# power_board.net
KiCad netlist of a schematic drawn in Altium Designer
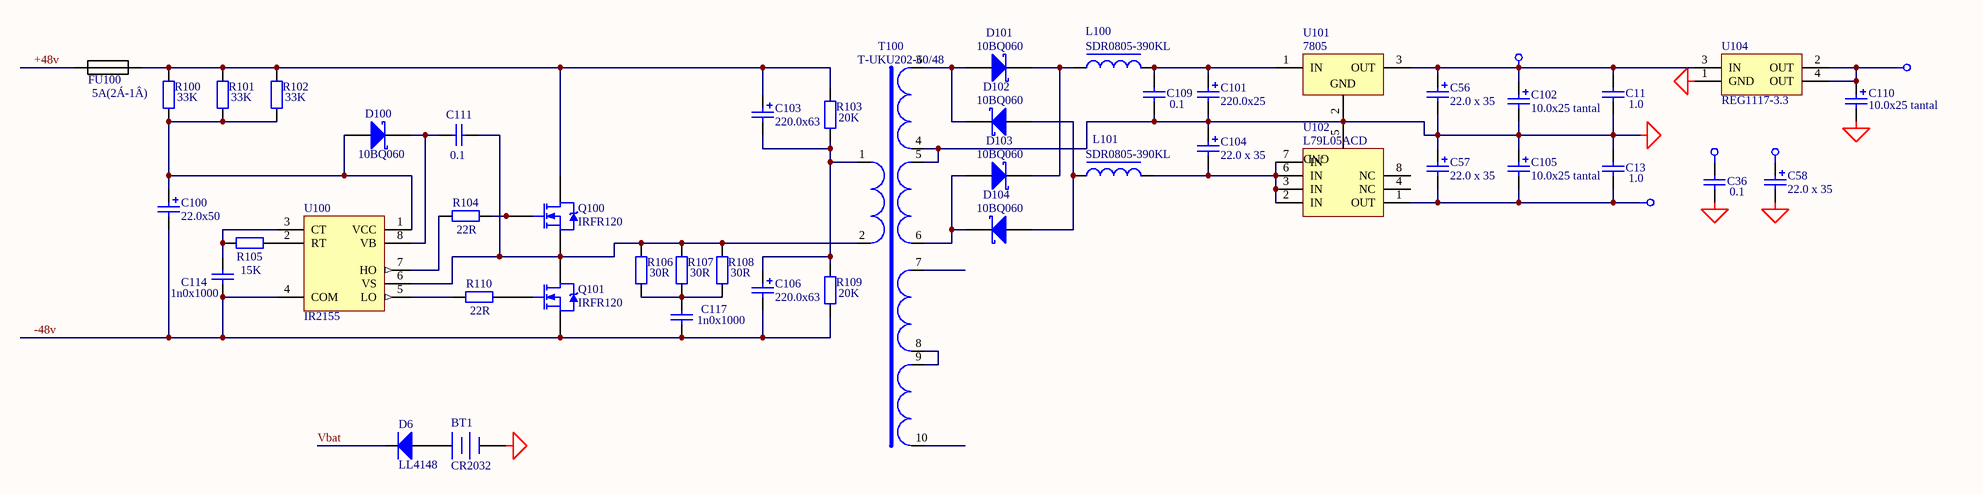
[diagram p0: power_board.SchDoc]

(export (version "E")
  (design (tool "Eeschema 10.0.6"))
  (components
    (comp (ref "BT1")
      (value "CR2032")
      (footprint "BAT_SUPP")
      (description "Multicell Battery")
      (fields (field (name "MANUFACTURER") "Generic Components") (field (name "PUBLISHER") "Altium Limited"))
      (libsource (lib "Miscellaneous Devices") (part "Battery"))
    )
    (comp (ref "C11")
      (value "1.0")
      (footprint "C3216-1206")
      (description "Capacitor (Semiconductor SIM Model)")
      (fields (field (name "MANUFACTURER") "Generic Components") (field (name "PUBLISHER") "Altium Limited"))
      (libsource (lib "Miscellaneous Devices") (part "Cap Semi"))
    )
    (comp (ref "C13")
      (value "1.0")
      (footprint "C3216-1206")
      (description "Capacitor (Semiconductor SIM Model)")
      (fields (field (name "MANUFACTURER") "Generic Components") (field (name "PUBLISHER") "Altium Limited"))
      (libsource (lib "Miscellaneous Devices") (part "Cap Semi"))
    )
    (comp (ref "C36")
      (value "0.1")
      (footprint "C3216-1206")
      (description "Capacitor (Semiconductor SIM Model)")
      (fields (field (name "MANUFACTURER") "Generic Components") (field (name "PUBLISHER") "Altium Limited"))
      (libsource (lib "Miscellaneous Devices") (part "Cap Semi"))
    )
    (comp (ref "C56")
      (value "22.0 x 35")
      (footprint "el3")
      (description "Polarized Capacitor (Radial)")
      (fields (field (name "MANUFACTURER") "Generic Components") (field (name "PUBLISHER") "Altium Limited"))
      (libsource (lib "PAL") (part "Cap Pol1"))
    )
    (comp (ref "C57")
      (value "22.0 x 35")
      (footprint "el3")
      (description "Polarized Capacitor (Radial)")
      (fields (field (name "MANUFACTURER") "Generic Components") (field (name "PUBLISHER") "Altium Limited"))
      (libsource (lib "PAL") (part "Cap Pol1"))
    )
    (comp (ref "C58")
      (value "22.0 x 35")
      (footprint "el3")
      (description "Polarized Capacitor (Radial)")
      (fields (field (name "MANUFACTURER") "Generic Components") (field (name "PUBLISHER") "Altium Limited"))
      (libsource (lib "PAL") (part "Cap Pol1"))
    )
    (comp (ref "C100")
      (value "22.0x50")
      (footprint "el3")
      (description "Polarized Capacitor (Radial)")
      (fields (field (name "MANUFACTURER") "Generic Components") (field (name "PUBLISHER") "Altium Limited"))
      (libsource (lib "PAL") (part "Cap Pol1"))
    )
    (comp (ref "C101")
      (value "220.0x25")
      (footprint "el5")
      (description "Polarized Capacitor (Radial)")
      (fields (field (name "MANUFACTURER") "Generic Components") (field (name "PUBLISHER") "Altium Limited"))
      (libsource (lib "PAL") (part "Cap Pol1"))
    )
    (comp (ref "C102")
      (value "10.0x25 tantal")
      (footprint "CAP_EL_6_3")
      (description "Polarized Capacitor (Radial)")
      (fields (field (name "MANUFACTURER") "Generic Components") (field (name "PUBLISHER") "Altium Limited"))
      (libsource (lib "PAL") (part "Cap Pol1"))
    )
    (comp (ref "C103")
      (value "220.0x63")
      (footprint "el5")
      (description "Polarized Capacitor (Radial)")
      (fields (field (name "MANUFACTURER") "Generic Components") (field (name "PUBLISHER") "Altium Limited"))
      (libsource (lib "PAL") (part "Cap Pol1"))
    )
    (comp (ref "C104")
      (value "22.0 x 35")
      (footprint "el3")
      (description "Polarized Capacitor (Radial)")
      (fields (field (name "MANUFACTURER") "Generic Components") (field (name "PUBLISHER") "Altium Limited"))
      (libsource (lib "PAL") (part "Cap Pol1"))
    )
    (comp (ref "C105")
      (value "10.0x25 tantal")
      (footprint "CAP_EL_6_3")
      (description "Polarized Capacitor (Radial)")
      (fields (field (name "MANUFACTURER") "Generic Components") (field (name "PUBLISHER") "Altium Limited"))
      (libsource (lib "PAL") (part "Cap Pol1"))
    )
    (comp (ref "C106")
      (value "220.0x63")
      (footprint "el5")
      (description "Polarized Capacitor (Radial)")
      (fields (field (name "MANUFACTURER") "Generic Components") (field (name "PUBLISHER") "Altium Limited"))
      (libsource (lib "PAL") (part "Cap Pol1"))
    )
    (comp (ref "C109")
      (value "0.1")
      (footprint "C3216-1206")
      (description "Capacitor (Semiconductor SIM Model)")
      (fields (field (name "MANUFACTURER") "Generic Components") (field (name "PUBLISHER") "Altium Limited"))
      (libsource (lib "Miscellaneous Devices") (part "Cap Semi"))
    )
    (comp (ref "C110")
      (value "10.0x25 tantal")
      (footprint "CAP_EL_6_3")
      (description "Polarized Capacitor (Radial)")
      (fields (field (name "MANUFACTURER") "Generic Components") (field (name "PUBLISHER") "Altium Limited"))
      (libsource (lib "PAL") (part "Cap Pol1"))
    )
    (comp (ref "C111")
      (value "0.1")
      (footprint "C3216-1206")
      (description "Capacitor (Semiconductor SIM Model)")
      (fields (field (name "MANUFACTURER") "Generic Components") (field (name "PUBLISHER") "Altium Limited"))
      (libsource (lib "Miscellaneous Devices") (part "Cap Semi"))
    )
    (comp (ref "C114")
      (value "1n0x1000")
      (footprint "_1206")
      (description "Capacitor (Semiconductor SIM Model)")
      (fields (field (name "MANUFACTURER") "Generic Components") (field (name "PUBLISHER") "Altium Limited"))
      (libsource (lib "Miscellaneous Devices") (part "Cap Semi"))
    )
    (comp (ref "C117")
      (value "1n0x1000")
      (footprint "_1206")
      (description "Capacitor (Semiconductor SIM Model)")
      (fields (field (name "MANUFACTURER") "Generic Components") (field (name "PUBLISHER") "Altium Limited"))
      (libsource (lib "Miscellaneous Devices") (part "Cap Semi"))
    )
    (comp (ref "D6")
      (value "LL4148")
      (footprint "_1206d")
      (description "Default Diode")
      (fields (field (name "MANUFACTURER") "Generic Components") (field (name "PUBLISHER") "Altium Limited"))
      (libsource (lib "PAL") (part "Diode"))
    )
    (comp (ref "D100")
      (value "10BQ060")
      (footprint "D_6_3")
      (description "Schottky Rectifier")
      (fields
        (field (name "MANUFACTURER") "International Rectifier")
        (field (name "PUBLISHER") "Altium Limited")
      )
      (libsource (lib "IR Discrete Diode") (part "10BQ015"))
    )
    (comp (ref "D101")
      (value "10BQ060")
      (footprint "D_6_3")
      (description "Schottky Rectifier")
      (fields
        (field (name "MANUFACTURER") "International Rectifier")
        (field (name "PUBLISHER") "Altium Limited")
      )
      (libsource (lib "IR Discrete Diode") (part "10BQ015"))
    )
    (comp (ref "D102")
      (value "10BQ060")
      (footprint "D_6_3")
      (description "Schottky Rectifier")
      (fields
        (field (name "MANUFACTURER") "International Rectifier")
        (field (name "PUBLISHER") "Altium Limited")
      )
      (libsource (lib "IR Discrete Diode") (part "10BQ015"))
    )
    (comp (ref "D103")
      (value "10BQ060")
      (footprint "D_6_3")
      (description "Schottky Rectifier")
      (fields
        (field (name "MANUFACTURER") "International Rectifier")
        (field (name "PUBLISHER") "Altium Limited")
      )
      (libsource (lib "IR Discrete Diode") (part "10BQ015"))
    )
    (comp (ref "D104")
      (value "10BQ060")
      (footprint "D_6_3")
      (description "Schottky Rectifier")
      (fields
        (field (name "MANUFACTURER") "International Rectifier")
        (field (name "PUBLISHER") "Altium Limited")
      )
      (libsource (lib "IR Discrete Diode") (part "10BQ015"))
    )
    (comp (ref "FU100") (value "5A(2Á-1Â)") (footprint "FUSE2") (libsource (lib "PAL") (part "FUSE")))
    (comp (ref "L100")
      (value "SDR0805-390KL")
      (footprint "L10x10")
      (description "Magnetic-Core Inductor")
      (fields (field (name "MANUFACTURER") "Generic Components") (field (name "PUBLISHER") "Altium Limited"))
      (libsource (lib "PAL") (part "Inductor Konstr 2"))
    )
    (comp (ref "L101")
      (value "SDR0805-390KL")
      (footprint "L10x10")
      (description "Magnetic-Core Inductor")
      (fields (field (name "MANUFACTURER") "Generic Components") (field (name "PUBLISHER") "Altium Limited"))
      (libsource (lib "PAL") (part "Inductor Konstr 2"))
    )
    (comp (ref "Q100")
      (value "IRFR120")
      (footprint "SIP-G3/E8")
      (description "HEXFET N-Channel Power MOSFET")
      (fields
        (field (name "MANUFACTURER") "International Rectifier")
        (field (name "PUBLISHER") "Altium Limited")
      )
      (libsource (lib "IR Discrete MOSFET") (part "IRFR120"))
    )
    (comp (ref "Q101")
      (value "IRFR120")
      (footprint "SIP-G3/E8")
      (description "HEXFET N-Channel Power MOSFET")
      (fields
        (field (name "MANUFACTURER") "International Rectifier")
        (field (name "PUBLISHER") "Altium Limited")
      )
      (libsource (lib "IR Discrete MOSFET") (part "IRFR120"))
    )
    (comp (ref "R100")
      (value "33K")
      (footprint "_1206")
      (description "Resistor")
      (fields (field (name "MANUFACTURER") "Generic Components") (field (name "PUBLISHER") "Altium Limited"))
      (libsource (lib "") (part "Res2_1"))
    )
    (comp (ref "R101")
      (value "33K")
      (footprint "_1206")
      (description "Resistor")
      (fields (field (name "MANUFACTURER") "Generic Components") (field (name "PUBLISHER") "Altium Limited"))
      (libsource (lib "") (part "Res2_1"))
    )
    (comp (ref "R102")
      (value "33K")
      (footprint "_1206")
      (description "Resistor")
      (fields (field (name "MANUFACTURER") "Generic Components") (field (name "PUBLISHER") "Altium Limited"))
      (libsource (lib "") (part "Res2_1"))
    )
    (comp (ref "R103")
      (value "20K")
      (footprint "_1206")
      (description "Resistor")
      (fields (field (name "MANUFACTURER") "Generic Components") (field (name "PUBLISHER") "Altium Limited"))
      (libsource (lib "") (part "Res2_1"))
    )
    (comp (ref "R104")
      (value "22R")
      (footprint "_1206")
      (description "Resistor")
      (fields (field (name "MANUFACTURER") "Generic Components") (field (name "PUBLISHER") "Altium Limited"))
      (libsource (lib "Miscellaneous Devices") (part "Res2"))
    )
    (comp (ref "R105")
      (value "15K")
      (footprint "_1206")
      (description "Resistor")
      (fields (field (name "MANUFACTURER") "Generic Components") (field (name "PUBLISHER") "Altium Limited"))
      (libsource (lib "Miscellaneous Devices") (part "Res2"))
    )
    (comp (ref "R106")
      (value "30R")
      (footprint "_1206")
      (description "Resistor")
      (fields (field (name "MANUFACTURER") "Generic Components") (field (name "PUBLISHER") "Altium Limited"))
      (libsource (lib "") (part "Res2_1"))
    )
    (comp (ref "R107")
      (value "30R")
      (footprint "_1206")
      (description "Resistor")
      (fields (field (name "MANUFACTURER") "Generic Components") (field (name "PUBLISHER") "Altium Limited"))
      (libsource (lib "") (part "Res2_1"))
    )
    (comp (ref "R108")
      (value "30R")
      (footprint "_1206")
      (description "Resistor")
      (fields (field (name "MANUFACTURER") "Generic Components") (field (name "PUBLISHER") "Altium Limited"))
      (libsource (lib "") (part "Res2_1"))
    )
    (comp (ref "R109")
      (value "20K")
      (footprint "_1206")
      (description "Resistor")
      (fields (field (name "MANUFACTURER") "Generic Components") (field (name "PUBLISHER") "Altium Limited"))
      (libsource (lib "") (part "Res2_1"))
    )
    (comp (ref "R110")
      (value "22R")
      (footprint "_1206")
      (description "Resistor")
      (fields (field (name "MANUFACTURER") "Generic Components") (field (name "PUBLISHER") "Altium Limited"))
      (libsource (lib "Miscellaneous Devices") (part "Res2"))
    )
    (comp (ref "T100")
      (value "T-UKU202-60/48")
      (footprint "trans_ring1")
      (libsource (lib "PAL") (part "TRANS_RING1"))
    )
    (comp (ref "U100")
      (value "IR2155")
      (footprint "DIP-8/D11")
      (description "Self-Oscillating Half-Bridge Driver")
      (fields
        (field (name "MANUFACTURER") "International Rectifier")
        (field (name "PUBLISHER") "Altium Limited")
      )
      (libsource (lib "IR Interface Bridge Driver") (part "IR2155"))
    )
    (comp (ref "U101")
      (value "7805")
      (footprint "D2PAK")
      (description "3-Terminal Positive Fixed Voltage Regulator")
      (fields (field (name "MANUFACTURER") "Motorola") (field (name "PUBLISHER") "Altium Limited"))
      (libsource (lib "PAL") (part "7805"))
    )
    (comp (ref "U102")
      (value "L79L05ACD")
      (footprint "SO-G8")
      (description "Negative Voltage Regulator")
      (fields (field (name "MANUFACTURER") "ST-Microelectronics") (field (name "PUBLISHER") "Altium Limited"))
      (libsource (lib "ST Power Mgt Voltage Regulator") (part "L79L05ACD"))
    )
    (comp (ref "U104")
      (value "REG1117-3.3")
      (footprint "SIP-G3/C7.4")
      (description "800mA and 1A Low Dropout Positive Regulator 2.85V, 3.3V, 5V, and Adjustable")
      (fields (field (name "MANUFACTURER") "Burr-Brown") (field (name "PUBLISHER") "Altium Limited"))
      (libsource (lib "BB Power Mgt Voltage Regulator") (part "REG1117-3.3"))
    )
  )
  (nets
    (net (code "1") (name "+3v3") (class "Default")
      (node (ref "C110") (pin "1") (pinfunction "1_1") (pintype "passive"))
      (node (ref "C36") (pin "2") (pinfunction "2_2") (pintype "passive"))
      (node (ref "C58") (pin "1") (pinfunction "1_1") (pintype "passive"))
      (node (ref "U104") (pin "2") (pinfunction "OUT_2") (pintype "power_in"))
      (node (ref "U104") (pin "4") (pinfunction "OUT_4") (pintype "power_in"))
    )
    (net (code "2") (name "+5v") (class "Default")
      (node (ref "C102") (pin "1") (pinfunction "1_1") (pintype "passive"))
      (node (ref "C11") (pin "2") (pinfunction "2_2") (pintype "passive"))
      (node (ref "C56") (pin "1") (pinfunction "1_1") (pintype "passive"))
      (node (ref "U101") (pin "3") (pinfunction "OUT_3") (pintype "power_in"))
      (node (ref "U104") (pin "3") (pinfunction "IN_3") (pintype "power_in"))
    )
    (net (code "3") (name "-5v") (class "Default")
      (node (ref "C105") (pin "2") (pinfunction "2_2") (pintype "passive"))
      (node (ref "C13") (pin "1") (pinfunction "1_1") (pintype "passive"))
      (node (ref "C57") (pin "2") (pinfunction "2_2") (pintype "passive"))
      (node (ref "U102") (pin "1") (pinfunction "OUT_1") (pintype "power_in"))
    )
    (net (code "4") (name "/+48v") (class "Default")
      (node (ref "FU100") (pin "1") (pinfunction "1_1") (pintype "passive"))
    )
    (net (code "5") (name "/-48v") (class "Default")
      (node (ref "C100") (pin "2") (pinfunction "2_2") (pintype "passive"))
      (node (ref "C106") (pin "2") (pinfunction "2_2") (pintype "passive"))
      (node (ref "C114") (pin "2") (pinfunction "2_2") (pintype "passive"))
      (node (ref "C117") (pin "2") (pinfunction "2_2") (pintype "passive"))
      (node (ref "Q101") (pin "3") (pinfunction "S_3") (pintype "passive"))
      (node (ref "R109") (pin "2") (pinfunction "2_2") (pintype "passive"))
      (node (ref "U100") (pin "4") (pinfunction "COM_4") (pintype "power_in"))
    )
    (net (code "6") (name "/Vbat") (class "Default")
      (node (ref "D6") (pin "2") (pinfunction "K_2") (pintype "passive"))
    )
    (net (code "7") (name "GND") (class "Default")
      (node (ref "BT1") (pin "2") (pinfunction "-_2") (pintype "passive"))
      (node (ref "C101") (pin "2") (pinfunction "2_2") (pintype "passive"))
      (node (ref "C102") (pin "2") (pinfunction "2_2") (pintype "passive"))
      (node (ref "C104") (pin "1") (pinfunction "1_1") (pintype "passive"))
      (node (ref "C105") (pin "1") (pinfunction "1_1") (pintype "passive"))
      (node (ref "C109") (pin "1") (pinfunction "1_1") (pintype "passive"))
      (node (ref "C11") (pin "1") (pinfunction "1_1") (pintype "passive"))
      (node (ref "C110") (pin "2") (pinfunction "2_2") (pintype "passive"))
      (node (ref "C13") (pin "2") (pinfunction "2_2") (pintype "passive"))
      (node (ref "C36") (pin "1") (pinfunction "1_1") (pintype "passive"))
      (node (ref "C56") (pin "2") (pinfunction "2_2") (pintype "passive"))
      (node (ref "C57") (pin "1") (pinfunction "1_1") (pintype "passive"))
      (node (ref "C58") (pin "2") (pinfunction "2_2") (pintype "passive"))
      (node (ref "T100") (pin "4") (pinfunction "Vss_4") (pintype "passive"))
      (node (ref "T100") (pin "5") (pinfunction "Vss_5") (pintype "passive"))
      (node (ref "U101") (pin "2") (pinfunction "GND_2") (pintype "power_in"))
      (node (ref "U102") (pin "5") (pinfunction "GND_5") (pintype "power_in"))
      (node (ref "U104") (pin "1") (pinfunction "GND_1") (pintype "power_in"))
    )
    (net (code "8") (name "Net-(BT1-+)") (class "Default")
      (node (ref "BT1") (pin "1") (pinfunction "+_1") (pintype "passive"))
      (node (ref "D6") (pin "1") (pinfunction "A_1") (pintype "passive"))
    )
    (net (code "9") (name "Net-(C103-Pad2)") (class "Default")
      (node (ref "C103") (pin "2") (pinfunction "2_2") (pintype "passive"))
      (node (ref "C106") (pin "1") (pinfunction "1_1") (pintype "passive"))
      (node (ref "R103") (pin "2") (pinfunction "2_2") (pintype "passive"))
      (node (ref "R109") (pin "1") (pinfunction "1_1") (pintype "passive"))
      (node (ref "T100") (pin "1") (pinfunction "Vss_1") (pintype "passive"))
    )
    (net (code "10") (name "Net-(C104-Pad2)") (class "Default")
      (node (ref "C104") (pin "2") (pinfunction "2_2") (pintype "passive"))
      (node (ref "L101") (pin "2") (pinfunction "2_2") (pintype "passive"))
      (node (ref "U102") (pin "2") (pinfunction "IN_2") (pintype "power_in"))
      (node (ref "U102") (pin "3") (pinfunction "IN_3") (pintype "power_in"))
      (node (ref "U102") (pin "6") (pinfunction "IN_6") (pintype "power_in"))
      (node (ref "U102") (pin "7") (pinfunction "IN_7") (pintype "power_in"))
    )
    (net (code "11") (name "Net-(C117-Pad1)") (class "Default")
      (node (ref "C117") (pin "1") (pinfunction "1_1") (pintype "passive"))
      (node (ref "R106") (pin "2") (pinfunction "2_2") (pintype "passive"))
      (node (ref "R107") (pin "2") (pinfunction "2_2") (pintype "passive"))
      (node (ref "R108") (pin "2") (pinfunction "2_2") (pintype "passive"))
    )
    (net (code "12") (name "Net-(D100-A)") (class "Default")
      (node (ref "C100") (pin "1") (pinfunction "1_1") (pintype "passive"))
      (node (ref "D100") (pin "1") (pinfunction "A_1") (pintype "passive"))
      (node (ref "R100") (pin "2") (pinfunction "2_2") (pintype "passive"))
      (node (ref "R101") (pin "2") (pinfunction "2_2") (pintype "passive"))
      (node (ref "R102") (pin "2") (pinfunction "2_2") (pintype "passive"))
      (node (ref "U100") (pin "1") (pinfunction "VCC_1") (pintype "power_in"))
    )
    (net (code "13") (name "Net-(D100-K)") (class "Default")
      (node (ref "C111") (pin "1") (pinfunction "1_1") (pintype "passive"))
      (node (ref "D100") (pin "2") (pinfunction "K_2") (pintype "passive"))
      (node (ref "U100") (pin "8") (pinfunction "VB_8") (pintype "power_in"))
    )
    (net (code "14") (name "Net-(D101-A)") (class "Default")
      (node (ref "D101") (pin "1") (pinfunction "A_1") (pintype "passive"))
      (node (ref "D102") (pin "2") (pinfunction "K_2") (pintype "passive"))
      (node (ref "T100") (pin "3") (pinfunction "Vss_3") (pintype "passive"))
    )
    (net (code "15") (name "Net-(D101-K)") (class "Default")
      (node (ref "D101") (pin "2") (pinfunction "K_2") (pintype "passive"))
      (node (ref "D103") (pin "2") (pinfunction "K_2") (pintype "passive"))
      (node (ref "L100") (pin "1") (pinfunction "1_1") (pintype "passive"))
    )
    (net (code "16") (name "Net-(D102-A)") (class "Default")
      (node (ref "D102") (pin "1") (pinfunction "A_1") (pintype "passive"))
      (node (ref "D104") (pin "1") (pinfunction "A_1") (pintype "passive"))
      (node (ref "L101") (pin "1") (pinfunction "1_1") (pintype "passive"))
    )
    (net (code "17") (name "Net-(D103-A)") (class "Default")
      (node (ref "D103") (pin "1") (pinfunction "A_1") (pintype "passive"))
      (node (ref "D104") (pin "2") (pinfunction "K_2") (pintype "passive"))
      (node (ref "T100") (pin "6") (pinfunction "Vss_6") (pintype "passive"))
    )
    (net (code "18") (name "Net-(Q100-D)") (class "Default")
      (node (ref "C103") (pin "1") (pinfunction "1_1") (pintype "passive"))
      (node (ref "FU100") (pin "2") (pinfunction "2_2") (pintype "passive"))
      (node (ref "Q100") (pin "4") (pinfunction "D_4") (pintype "passive"))
      (node (ref "R100") (pin "1") (pinfunction "1_1") (pintype "passive"))
      (node (ref "R101") (pin "1") (pinfunction "1_1") (pintype "passive"))
      (node (ref "R102") (pin "1") (pinfunction "1_1") (pintype "passive"))
      (node (ref "R103") (pin "1") (pinfunction "1_1") (pintype "passive"))
    )
    (net (code "19") (name "Net-(Q100-G)") (class "Default")
      (node (ref "Q100") (pin "1") (pinfunction "G_1") (pintype "passive"))
      (node (ref "R104") (pin "2") (pinfunction "2_2") (pintype "passive"))
    )
    (net (code "20") (name "Net-(Q100-S)") (class "Default")
      (node (ref "C111") (pin "2") (pinfunction "2_2") (pintype "passive"))
      (node (ref "Q100") (pin "3") (pinfunction "S_3") (pintype "passive"))
      (node (ref "Q101") (pin "4") (pinfunction "D_4") (pintype "passive"))
      (node (ref "R106") (pin "1") (pinfunction "1_1") (pintype "passive"))
      (node (ref "R107") (pin "1") (pinfunction "1_1") (pintype "passive"))
      (node (ref "R108") (pin "1") (pinfunction "1_1") (pintype "passive"))
      (node (ref "T100") (pin "2") (pinfunction "Vss_2") (pintype "passive"))
      (node (ref "U100") (pin "6") (pinfunction "VS_6") (pintype "power_in"))
    )
    (net (code "21") (name "Net-(Q101-G)") (class "Default")
      (node (ref "Q101") (pin "1") (pinfunction "G_1") (pintype "passive"))
      (node (ref "R110") (pin "2") (pinfunction "2_2") (pintype "passive"))
    )
    (net (code "22") (name "Net-(T100-Vss-Pad8)") (class "Default")
      (node (ref "T100") (pin "8") (pinfunction "Vss_8") (pintype "passive"))
      (node (ref "T100") (pin "9") (pinfunction "Vss_9") (pintype "passive"))
    )
    (net (code "23") (name "Net-(U100-CT)") (class "Default")
      (node (ref "C114") (pin "1") (pinfunction "1_1") (pintype "passive"))
      (node (ref "R105") (pin "1") (pinfunction "1_1") (pintype "passive"))
      (node (ref "U100") (pin "3") (pinfunction "CT_3") (pintype "passive"))
    )
    (net (code "24") (name "Net-(U100-HO)") (class "Default")
      (node (ref "R104") (pin "1") (pinfunction "1_1") (pintype "passive"))
      (node (ref "U100") (pin "7") (pinfunction "HO_7") (pintype "output"))
    )
    (net (code "25") (name "Net-(U100-LO)") (class "Default")
      (node (ref "R110") (pin "1") (pinfunction "1_1") (pintype "passive"))
      (node (ref "U100") (pin "5") (pinfunction "LO_5") (pintype "output"))
    )
    (net (code "26") (name "Net-(U100-RT)") (class "Default")
      (node (ref "R105") (pin "2") (pinfunction "2_2") (pintype "passive"))
      (node (ref "U100") (pin "2") (pinfunction "RT_2") (pintype "passive"))
    )
    (net (code "27") (name "Net-(U101-IN)") (class "Default")
      (node (ref "C101") (pin "1") (pinfunction "1_1") (pintype "passive"))
      (node (ref "C109") (pin "2") (pinfunction "2_2") (pintype "passive"))
      (node (ref "L100") (pin "2") (pinfunction "2_2") (pintype "passive"))
      (node (ref "U101") (pin "1") (pinfunction "IN_1") (pintype "power_in"))
    )
    (net (code "28") (name "unconnected-(T100-Vss-Pad7)") (class "Default")
      (node (ref "T100") (pin "7") (pinfunction "Vss_7") (pintype "passive"))
    )
    (net (code "29") (name "unconnected-(T100-Vss-Pad10)") (class "Default")
      (node (ref "T100") (pin "10") (pinfunction "Vss_10") (pintype "passive"))
    )
    (net (code "30") (name "unconnected-(U102-NC-Pad4)") (class "Default")
      (node (ref "U102") (pin "4") (pinfunction "NC_4") (pintype "passive"))
    )
    (net (code "31") (name "unconnected-(U102-NC-Pad8)") (class "Default")
      (node (ref "U102") (pin "8") (pinfunction "NC_8") (pintype "passive"))
    )
  )
)
